# tenka1.net
KiCad netlist of a schematic drawn in EAGLE
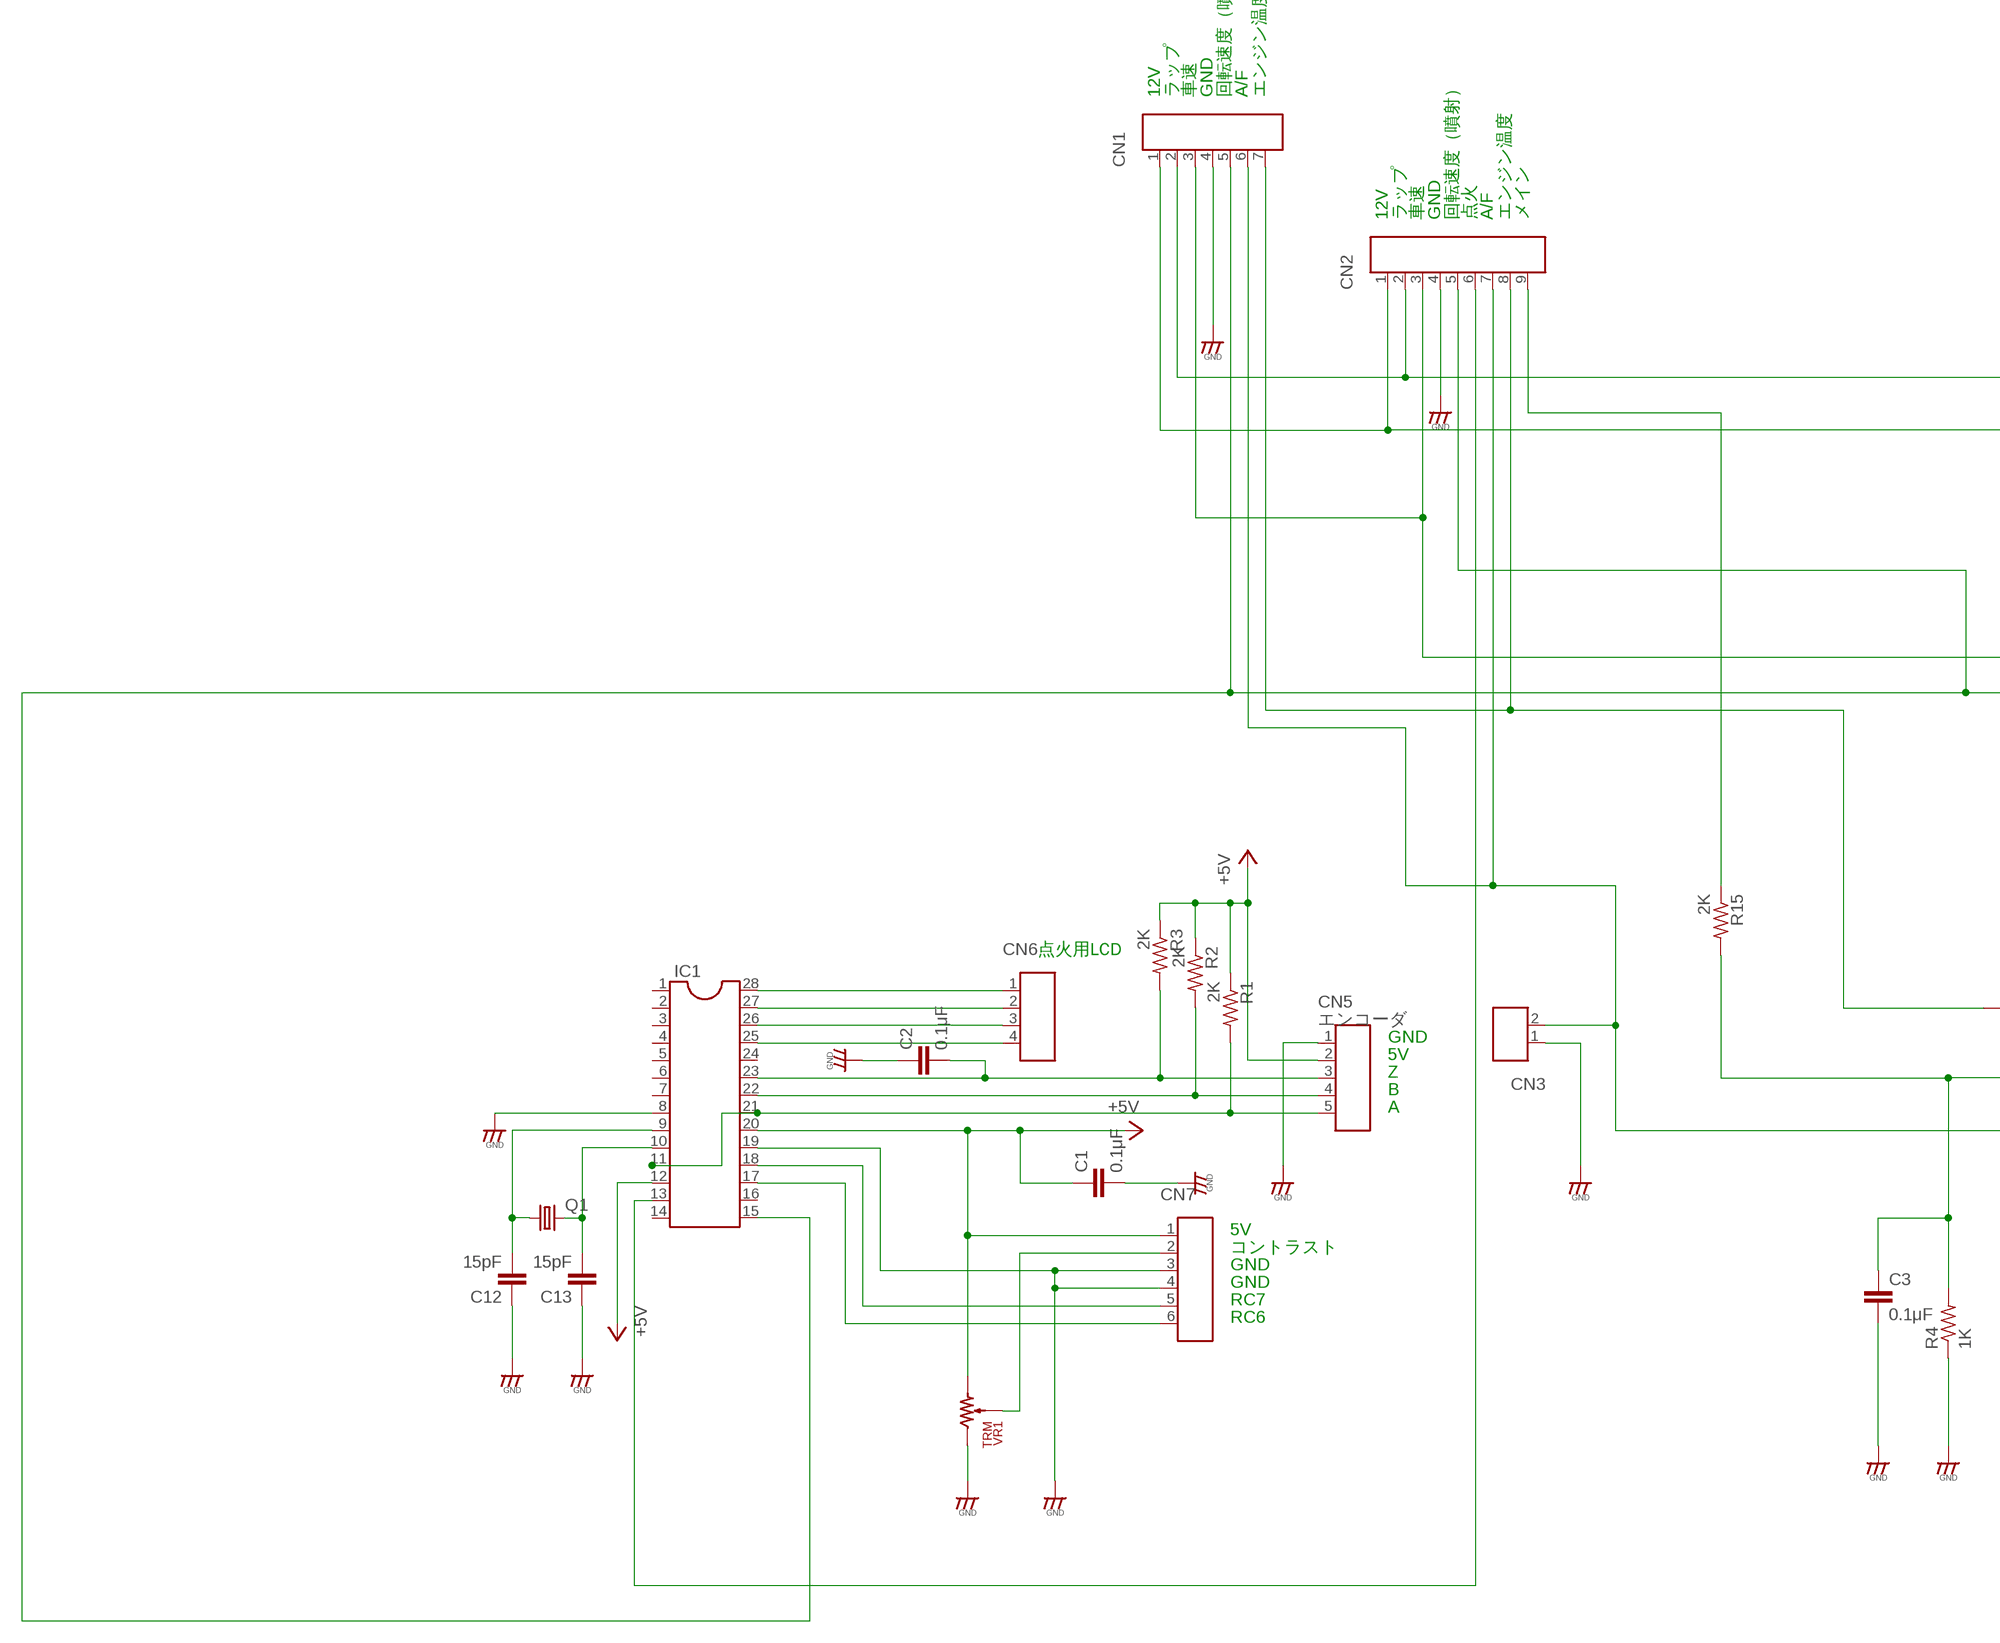
[diagram p0: schematic, sheet 1, part 1 of 2]
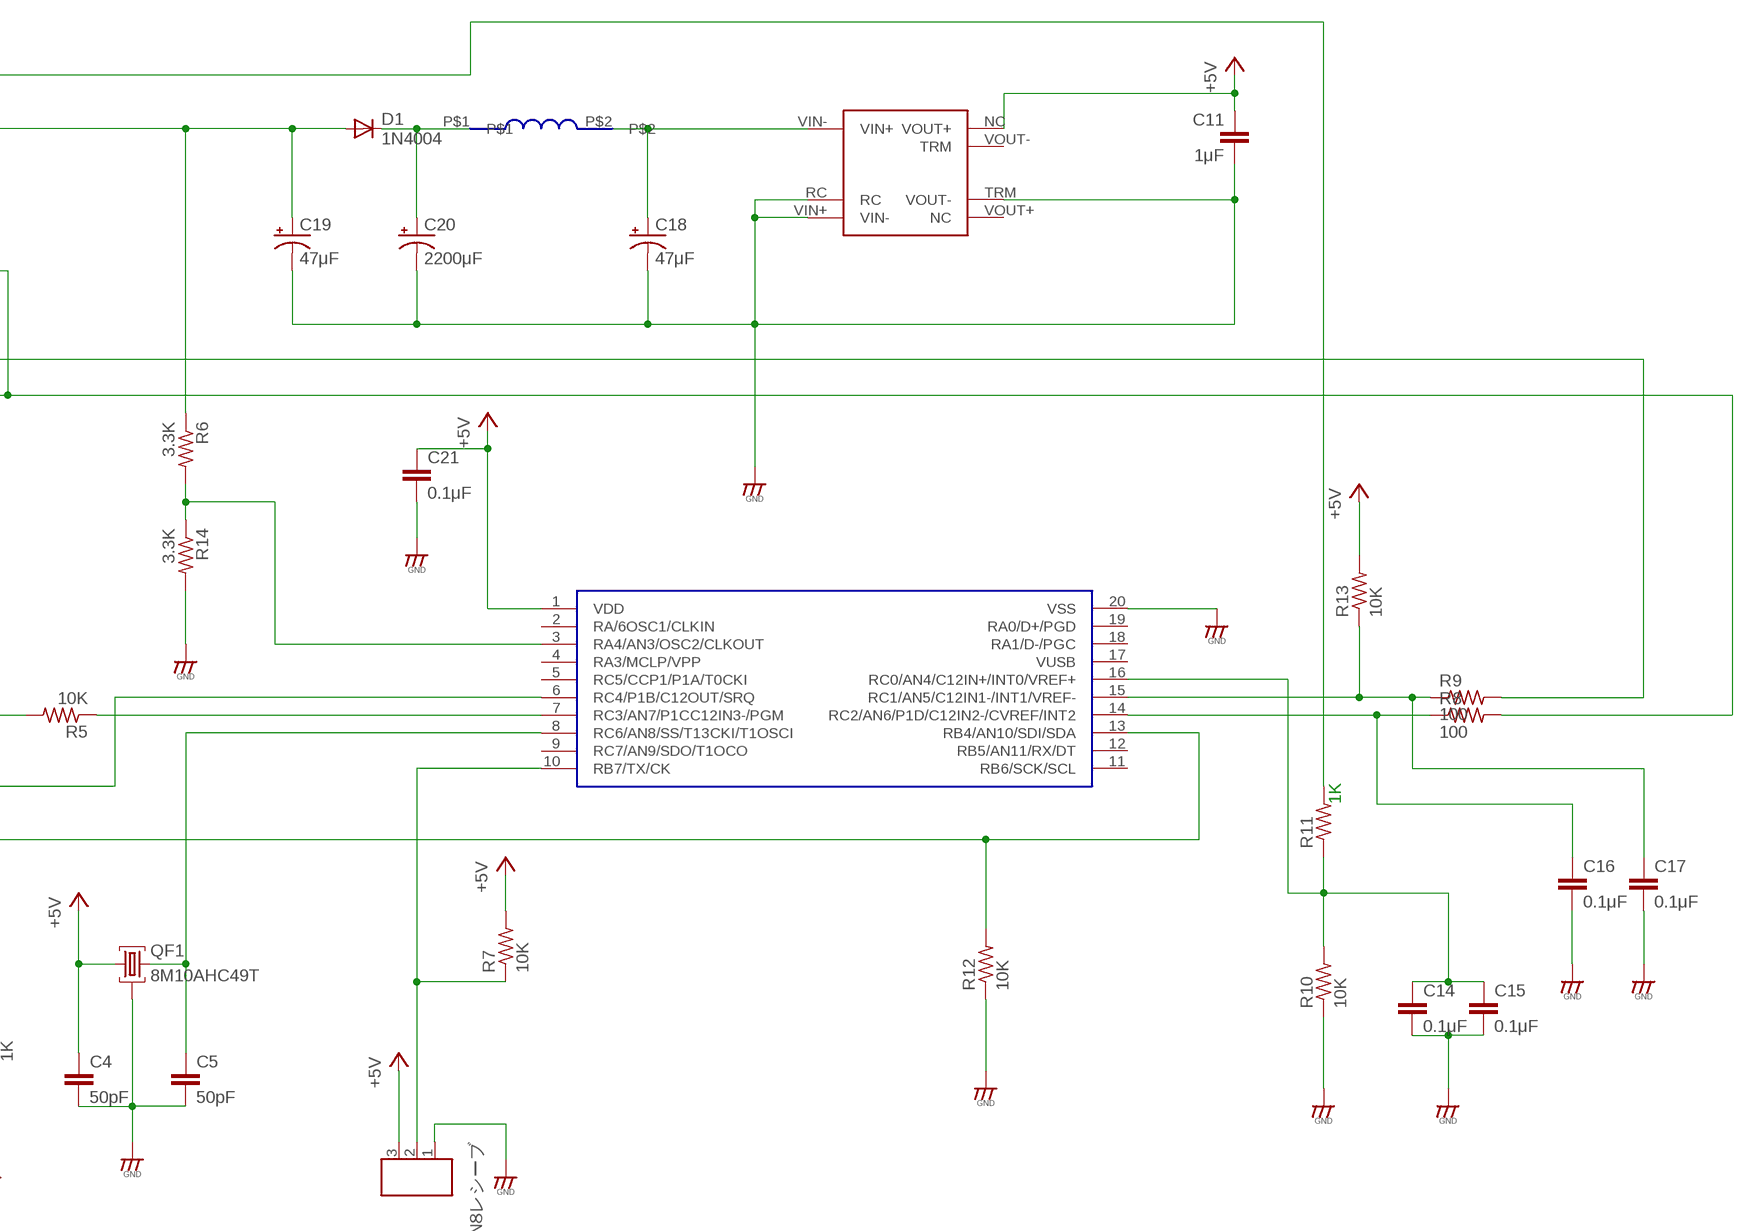
[diagram p1: schematic, sheet 1, part 2 of 2]

(export (version "E")
  (design (tool "Eeschema 10.0.6"))
  (components
    (comp (ref "18F14K50")
      (value "18F14K5018F14K50")
      (footprint "eagle-import:18F14K50")
      (libsource (lib "eagle-import") (part "18F14K5018F14K50"))
    )
    (comp (ref "C1")
      (value "0.1μF")
      (footprint "eagle-import:C025-024X044")
      (libsource (lib "eagle-import") (part "C-EU025-024X044"))
    )
    (comp (ref "C2")
      (value "0.1μF")
      (footprint "eagle-import:C025-024X044")
      (libsource (lib "eagle-import") (part "C-EU025-024X044"))
    )
    (comp (ref "C3")
      (value "0.1μF")
      (footprint "eagle-import:C025-024X044")
      (libsource (lib "eagle-import") (part "C-EU025-024X044"))
    )
    (comp (ref "C4")
      (value "50pF")
      (footprint "eagle-import:C025-024X044")
      (libsource (lib "eagle-import") (part "C-EU025-024X044"))
    )
    (comp (ref "C5")
      (value "50pF")
      (footprint "eagle-import:C025-024X044")
      (libsource (lib "eagle-import") (part "C-EU025-024X044"))
    )
    (comp (ref "C11")
      (value "1μF")
      (footprint "eagle-import:C025-024X044")
      (libsource (lib "eagle-import") (part "C-EU025-024X044"))
    )
    (comp (ref "C12")
      (value "15pF")
      (footprint "eagle-import:C025-024X044")
      (libsource (lib "eagle-import") (part "C-EU025-024X044"))
    )
    (comp (ref "C13")
      (value "15pF")
      (footprint "eagle-import:C025-024X044")
      (libsource (lib "eagle-import") (part "C-EU025-024X044"))
    )
    (comp (ref "C14")
      (value "0.1μF")
      (footprint "eagle-import:C025-024X044")
      (libsource (lib "eagle-import") (part "C-EU025-024X044"))
    )
    (comp (ref "C15")
      (value "0.1μF")
      (footprint "eagle-import:C025-024X044")
      (libsource (lib "eagle-import") (part "C-EU025-024X044"))
    )
    (comp (ref "C16")
      (value "0.1μF")
      (footprint "eagle-import:C025-024X044")
      (libsource (lib "eagle-import") (part "C-EU025-024X044"))
    )
    (comp (ref "C17")
      (value "0.1μF")
      (footprint "eagle-import:C025-024X044")
      (libsource (lib "eagle-import") (part "C-EU025-024X044"))
    )
    (comp (ref "C18")
      (value "47μF")
      (footprint "eagle-import:E2-4")
      (libsource (lib "eagle-import") (part "CPOL-USE2-4"))
    )
    (comp (ref "C19")
      (value "47μF")
      (footprint "eagle-import:E2-4")
      (libsource (lib "eagle-import") (part "CPOL-USE2-4"))
    )
    (comp (ref "C20")
      (value "2200μF")
      (footprint "eagle-import:E5-13")
      (libsource (lib "eagle-import") (part "CPOL-USE5-13"))
    )
    (comp (ref "C21")
      (value "0.1μF")
      (footprint "eagle-import:C025-024X044")
      (libsource (lib "eagle-import") (part "C-EU025-024X044"))
    )
    (comp (ref "CN1")
      (value "CON_7P")
      (footprint "eagle-import:CON_HRS_DIP_7")
      (libsource (lib "eagle-import") (part "CON_7P"))
    )
    (comp (ref "CN2")
      (value "CON_9P")
      (footprint "eagle-import:CON_HRS_DIP_9")
      (libsource (lib "eagle-import") (part "CON_9P"))
    )
    (comp (ref "CN3")
      (value "CON_2P")
      (footprint "eagle-import:CON_HRS_DIP_2")
      (libsource (lib "eagle-import") (part "CON_2P"))
    )
    (comp (ref "CN5")
      (value "エンコーダ")
      (footprint "eagle-import:CON_HRS_DIP_5")
      (libsource (lib "eagle-import") (part "CON_5P"))
    )
    (comp (ref "CN6")
      (value "CON_4P")
      (footprint "eagle-import:CON_HRS_DIP_4")
      (libsource (lib "eagle-import") (part "CON_4P"))
    )
    (comp (ref "CN7")
      (value "CON_6P")
      (footprint "eagle-import:CON_HRS_DIP_6")
      (libsource (lib "eagle-import") (part "CON_6P"))
    )
    (comp (ref "CN8レシーブ")
      (value "CON_3P")
      (footprint "eagle-import:CON_HRS_DIP_3")
      (libsource (lib "eagle-import") (part "CON_3P"))
    )
    (comp (ref "D1")
      (value "1N4004")
      (footprint "eagle-import:DO41-10")
      (libsource (lib "eagle-import") (part "1N4004"))
    )
    (comp (ref "DC2")
      (value "DCDC_NEW")
      (footprint "eagle-import:DCDC_NEW")
      (libsource (lib "eagle-import") (part "DCDC_NEW"))
    )
    (comp (ref "IC1")
      (value "DIL28-3")
      (footprint "eagle-import:DIL28-3")
      (libsource (lib "eagle-import") (part "DIL28-3"))
    )
    (comp (ref "LHL13NB101K1")
      (value "LHL13NB101KLHL13NB101K")
      (footprint "eagle-import:LHL13NB101K")
      (libsource (lib "eagle-import") (part "LHL13NB101KLHL13NB101K"))
    )
    (comp (ref "Q1")
      (value "CRYSTALHC49S")
      (footprint "eagle-import:HC49_S")
      (libsource (lib "eagle-import") (part "CRYSTALHC49S"))
    )
    (comp (ref "QF1")
      (value "8M10AHC49T")
      (footprint "eagle-import:HC49U")
      (libsource (lib "eagle-import") (part "8M10AHC49T"))
    )
    (comp (ref "R1")
      (value "2K")
      (footprint "eagle-import:0207_7")
      (libsource (lib "eagle-import") (part "R-US_0207/7"))
    )
    (comp (ref "R2")
      (value "2K")
      (footprint "eagle-import:0207_7")
      (libsource (lib "eagle-import") (part "R-US_0207/7"))
    )
    (comp (ref "R3")
      (value "2K")
      (footprint "eagle-import:0207_7")
      (libsource (lib "eagle-import") (part "R-US_0207/7"))
    )
    (comp (ref "R4")
      (value "1K")
      (footprint "eagle-import:0207_7")
      (libsource (lib "eagle-import") (part "R-US_0207/7"))
    )
    (comp (ref "R5")
      (value "10K")
      (footprint "eagle-import:0207_7")
      (libsource (lib "eagle-import") (part "R-US_0207/7"))
    )
    (comp (ref "R6")
      (value "3.3K")
      (footprint "eagle-import:0207_7")
      (libsource (lib "eagle-import") (part "R-US_0207/7"))
    )
    (comp (ref "R7")
      (value "10K")
      (footprint "eagle-import:0207_7")
      (libsource (lib "eagle-import") (part "R-US_0207/7"))
    )
    (comp (ref "R8")
      (value "100")
      (footprint "eagle-import:0207_7")
      (libsource (lib "eagle-import") (part "R-US_0207/7"))
    )
    (comp (ref "R9")
      (value "100")
      (footprint "eagle-import:0207_7")
      (libsource (lib "eagle-import") (part "R-US_0207/7"))
    )
    (comp (ref "R10")
      (value "10K")
      (footprint "eagle-import:0207_7")
      (libsource (lib "eagle-import") (part "R-US_0207/7"))
    )
    (comp (ref "R11")
      (value "R-US_0207/7")
      (footprint "eagle-import:0207_7")
      (libsource (lib "eagle-import") (part "R-US_0207/7"))
    )
    (comp (ref "R12")
      (value "10K")
      (footprint "eagle-import:0207_7")
      (libsource (lib "eagle-import") (part "R-US_0207/7"))
    )
    (comp (ref "R13")
      (value "10K")
      (footprint "eagle-import:0207_7")
      (libsource (lib "eagle-import") (part "R-US_0207/7"))
    )
    (comp (ref "R14")
      (value "3.3K")
      (footprint "eagle-import:0207_7")
      (libsource (lib "eagle-import") (part "R-US_0207/7"))
    )
    (comp (ref "R15")
      (value "2K")
      (footprint "eagle-import:0207_7")
      (libsource (lib "eagle-import") (part "R-US_0207/7"))
    )
    (comp (ref "VR1")
      (value "TRM")
      (footprint "eagle-import:TRM")
      (libsource (lib "eagle-import") (part "TRM"))
    )
  )
  (nets
    (net (code "1") (name "+5V") (class "Default")
      (node (ref "18F14K50") (pin "1") (pinfunction "VDD_1") (pintype "bidirectional"))
      (node (ref "C1") (pin "1") (pinfunction "1_1") (pintype "passive"))
      (node (ref "C11") (pin "1") (pinfunction "1_1") (pintype "passive"))
      (node (ref "C21") (pin "1") (pinfunction "1_1") (pintype "passive"))
      (node (ref "C4") (pin "1") (pinfunction "1_1") (pintype "passive"))
      (node (ref "CN5") (pin "2") (pinfunction "2_2") (pintype "passive"))
      (node (ref "CN7") (pin "1") (pinfunction "1_1") (pintype "passive"))
      (node (ref "CN8レシーブ") (pin "3") (pinfunction "3_3") (pintype "passive"))
      (node (ref "DC2") (pin "NC") (pinfunction "VOUT+_NC") (pintype "bidirectional"))
      (node (ref "IC1") (pin "12") (pinfunction "12_12") (pintype "passive"))
      (node (ref "IC1") (pin "20") (pinfunction "20_20") (pintype "passive"))
      (node (ref "QF1") (pin "1") (pinfunction "1_1") (pintype "passive"))
      (node (ref "R1") (pin "1") (pinfunction "1_1") (pintype "passive"))
      (node (ref "R13") (pin "2") (pinfunction "2_2") (pintype "passive"))
      (node (ref "R2") (pin "1") (pinfunction "1_1") (pintype "passive"))
      (node (ref "R3") (pin "1") (pinfunction "1_1") (pintype "passive"))
      (node (ref "R7") (pin "2") (pinfunction "2_2") (pintype "passive"))
      (node (ref "VR1") (pin "P$1") (pinfunction "P$1_P$1") (pintype "passive"))
    )
    (net (code "2") (name "GND") (class "Default")
      (node (ref "18F14K50") (pin "20") (pinfunction "VSS_20") (pintype "bidirectional"))
      (node (ref "C1") (pin "2") (pinfunction "2_2") (pintype "passive"))
      (node (ref "C11") (pin "2") (pinfunction "2_2") (pintype "passive"))
      (node (ref "C12") (pin "1") (pinfunction "1_1") (pintype "passive"))
      (node (ref "C13") (pin "1") (pinfunction "1_1") (pintype "passive"))
      (node (ref "C14") (pin "2") (pinfunction "2_2") (pintype "passive"))
      (node (ref "C15") (pin "2") (pinfunction "2_2") (pintype "passive"))
      (node (ref "C16") (pin "2") (pinfunction "2_2") (pintype "passive"))
      (node (ref "C17") (pin "2") (pinfunction "2_2") (pintype "passive"))
      (node (ref "C18") (pin "-") (pinfunction "-_-") (pintype "passive"))
      (node (ref "C19") (pin "-") (pinfunction "-_-") (pintype "passive"))
      (node (ref "C2") (pin "1") (pinfunction "1_1") (pintype "passive"))
      (node (ref "C20") (pin "-") (pinfunction "-_-") (pintype "passive"))
      (node (ref "C21") (pin "2") (pinfunction "2_2") (pintype "passive"))
      (node (ref "C3") (pin "2") (pinfunction "2_2") (pintype "passive"))
      (node (ref "C4") (pin "2") (pinfunction "2_2") (pintype "passive"))
      (node (ref "C5") (pin "2") (pinfunction "2_2") (pintype "passive"))
      (node (ref "CN1") (pin "4") (pinfunction "4_4") (pintype "passive"))
      (node (ref "CN2") (pin "4") (pinfunction "4_4") (pintype "passive"))
      (node (ref "CN3") (pin "1") (pinfunction "1_1") (pintype "passive"))
      (node (ref "CN5") (pin "1") (pinfunction "1_1") (pintype "passive"))
      (node (ref "CN7") (pin "3") (pinfunction "3_3") (pintype "passive"))
      (node (ref "CN7") (pin "4") (pinfunction "4_4") (pintype "passive"))
      (node (ref "CN8レシーブ") (pin "1") (pinfunction "1_1") (pintype "passive"))
      (node (ref "DC2") (pin "RC") (pinfunction "RC_RC") (pintype "bidirectional"))
      (node (ref "DC2") (pin "TRM") (pinfunction "VOUT-_TRM") (pintype "bidirectional"))
      (node (ref "DC2") (pin "VIN+") (pinfunction "VIN-_VIN+") (pintype "bidirectional"))
      (node (ref "IC1") (pin "19") (pinfunction "19_19") (pintype "passive"))
      (node (ref "IC1") (pin "8") (pinfunction "8_8") (pintype "passive"))
      (node (ref "QF1") (pin "2") (pinfunction "2_2") (pintype "passive"))
      (node (ref "R10") (pin "1") (pinfunction "1_1") (pintype "passive"))
      (node (ref "R12") (pin "1") (pinfunction "1_1") (pintype "passive"))
      (node (ref "R14") (pin "2") (pinfunction "2_2") (pintype "passive"))
      (node (ref "R4") (pin "1") (pinfunction "1_1") (pintype "passive"))
      (node (ref "VR1") (pin "P$3") (pinfunction "P$3_P$3") (pintype "passive"))
    )
    (net (code "3") (name "Net-(18F14K50-RA4{slash}AN3{slash}OSC2{slash}CLKOUT)") (class "Default")
      (node (ref "18F14K50") (pin "3") (pinfunction "RA4/AN3/OSC2/CLKOUT_3") (pintype "bidirectional"))
      (node (ref "R14") (pin "1") (pinfunction "1_1") (pintype "passive"))
      (node (ref "R6") (pin "2") (pinfunction "2_2") (pintype "passive"))
    )
    (net (code "4") (name "Net-(18F14K50-RB4{slash}AN10{slash}SDI{slash}SDA)") (class "Default")
      (node (ref "18F14K50") (pin "13") (pinfunction "RB4/AN10/SDI/SDA_13") (pintype "bidirectional"))
      (node (ref "CN1") (pin "6") (pinfunction "6_6") (pintype "passive"))
      (node (ref "CN2") (pin "7") (pinfunction "7_7") (pintype "passive"))
      (node (ref "CN3") (pin "2") (pinfunction "2_2") (pintype "passive"))
      (node (ref "R12") (pin "2") (pinfunction "2_2") (pintype "passive"))
    )
    (net (code "5") (name "Net-(18F14K50-RB7{slash}TX{slash}CK)") (class "Default")
      (node (ref "18F14K50") (pin "10") (pinfunction "RB7/TX/CK_10") (pintype "bidirectional"))
      (node (ref "CN8レシーブ") (pin "2") (pinfunction "2_2") (pintype "passive"))
      (node (ref "R7") (pin "1") (pinfunction "1_1") (pintype "passive"))
    )
    (net (code "6") (name "Net-(18F14K50-RC0{slash}AN4{slash}C12IN+{slash}INT0{slash}VREF+)") (class "Default")
      (node (ref "18F14K50") (pin "16") (pinfunction "RC0/AN4/C12IN+/INT0/VREF+_16") (pintype "bidirectional"))
      (node (ref "C14") (pin "1") (pinfunction "1_1") (pintype "passive"))
      (node (ref "C15") (pin "1") (pinfunction "1_1") (pintype "passive"))
      (node (ref "R10") (pin "2") (pinfunction "2_2") (pintype "passive"))
      (node (ref "R11") (pin "1") (pinfunction "1_1") (pintype "passive"))
    )
    (net (code "7") (name "Net-(18F14K50-RC1{slash}AN5{slash}C12IN1-{slash}INT1{slash}VREF-)") (class "Default")
      (node (ref "18F14K50") (pin "15") (pinfunction "RC1/AN5/C12IN1-/INT1/VREF-_15") (pintype "bidirectional"))
      (node (ref "C17") (pin "1") (pinfunction "1_1") (pintype "passive"))
      (node (ref "R13") (pin "1") (pinfunction "1_1") (pintype "passive"))
      (node (ref "R9") (pin "1") (pinfunction "1_1") (pintype "passive"))
    )
    (net (code "8") (name "Net-(18F14K50-RC2{slash}AN6{slash}P1D{slash}C12IN2-{slash}CVREF{slash}INT2)") (class "Default")
      (node (ref "18F14K50") (pin "14") (pinfunction "RC2/AN6/P1D/C12IN2-/CVREF/INT2_14") (pintype "bidirectional"))
      (node (ref "C16") (pin "1") (pinfunction "1_1") (pintype "passive"))
      (node (ref "R8") (pin "1") (pinfunction "1_1") (pintype "passive"))
    )
    (net (code "9") (name "Net-(18F14K50-RC3{slash}AN7{slash}P1CC12IN3-{slash}PGM)") (class "Default")
      (node (ref "18F14K50") (pin "7") (pinfunction "RC3/AN7/P1CC12IN3-/PGM_7") (pintype "bidirectional"))
      (node (ref "R5") (pin "1") (pinfunction "1_1") (pintype "passive"))
    )
    (net (code "10") (name "Net-(18F14K50-RC4{slash}P1B{slash}C12OUT{slash}SRQ)") (class "Default")
      (node (ref "18F14K50") (pin "6") (pinfunction "RC4/P1B/C12OUT/SRQ_6") (pintype "bidirectional"))
      (node (ref "C3") (pin "1") (pinfunction "1_1") (pintype "passive"))
      (node (ref "R15") (pin "2") (pinfunction "2_2") (pintype "passive"))
      (node (ref "R4") (pin "2") (pinfunction "2_2") (pintype "passive"))
    )
    (net (code "11") (name "Net-(18F14K50-RC6{slash}AN8{slash}SS{slash}T13CKI{slash}T1OSCI)") (class "Default")
      (node (ref "18F14K50") (pin "8") (pinfunction "RC6/AN8/SS/T13CKI/T1OSCI_8") (pintype "bidirectional"))
      (node (ref "C5") (pin "1") (pinfunction "1_1") (pintype "passive"))
      (node (ref "QF1") (pin "3") (pinfunction "3_3") (pintype "passive"))
    )
    (net (code "12") (name "Net-(C2-Pad2)") (class "Default")
      (node (ref "C2") (pin "2") (pinfunction "2_2") (pintype "passive"))
      (node (ref "CN5") (pin "3") (pinfunction "3_3") (pintype "passive"))
      (node (ref "IC1") (pin "23") (pinfunction "23_23") (pintype "passive"))
      (node (ref "R3") (pin "2") (pinfunction "2_2") (pintype "passive"))
    )
    (net (code "13") (name "Net-(C12-Pad2)") (class "Default")
      (node (ref "C12") (pin "2") (pinfunction "2_2") (pintype "passive"))
      (node (ref "IC1") (pin "9") (pinfunction "9_9") (pintype "passive"))
      (node (ref "Q1") (pin "1") (pinfunction "1_1") (pintype "passive"))
    )
    (net (code "14") (name "Net-(C13-Pad2)") (class "Default")
      (node (ref "C13") (pin "2") (pinfunction "2_2") (pintype "passive"))
      (node (ref "IC1") (pin "10") (pinfunction "10_10") (pintype "passive"))
      (node (ref "Q1") (pin "2") (pinfunction "2_2") (pintype "passive"))
    )
    (net (code "15") (name "Net-(C19-Pad+)") (class "Default")
      (node (ref "C19") (pin "+") (pinfunction "+_+") (pintype "passive"))
      (node (ref "CN1") (pin "1") (pinfunction "1_1") (pintype "passive"))
      (node (ref "CN2") (pin "1") (pinfunction "1_1") (pintype "passive"))
      (node (ref "D1") (pin "A") (pinfunction "A_A") (pintype "passive"))
      (node (ref "R6") (pin "1") (pinfunction "1_1") (pintype "passive"))
    )
    (net (code "16") (name "Net-(C20-Pad+)") (class "Default")
      (node (ref "C20") (pin "+") (pinfunction "+_+") (pintype "passive"))
      (node (ref "D1") (pin "C") (pinfunction "C_C") (pintype "passive"))
      (node (ref "LHL13NB101K1") (pin "P$1") (pinfunction "P$1_P$1") (pintype "bidirectional"))
    )
    (net (code "17") (name "Net-(CN1-Pad2)") (class "Default")
      (node (ref "CN1") (pin "2") (pinfunction "2_2") (pintype "passive"))
      (node (ref "CN2") (pin "2") (pinfunction "2_2") (pintype "passive"))
      (node (ref "R11") (pin "2") (pinfunction "2_2") (pintype "passive"))
    )
    (net (code "18") (name "Net-(CN1-Pad3)") (class "Default")
      (node (ref "CN1") (pin "3") (pinfunction "3_3") (pintype "passive"))
      (node (ref "CN2") (pin "3") (pinfunction "3_3") (pintype "passive"))
      (node (ref "R9") (pin "2") (pinfunction "2_2") (pintype "passive"))
    )
    (net (code "19") (name "Net-(CN1-Pad5)") (class "Default")
      (node (ref "CN1") (pin "5") (pinfunction "5_5") (pintype "passive"))
      (node (ref "CN2") (pin "5") (pinfunction "5_5") (pintype "passive"))
      (node (ref "IC1") (pin "15") (pinfunction "15_15") (pintype "passive"))
      (node (ref "R8") (pin "2") (pinfunction "2_2") (pintype "passive"))
    )
    (net (code "20") (name "Net-(CN1-Pad7)") (class "Default")
      (node (ref "CN1") (pin "7") (pinfunction "7_7") (pintype "passive"))
      (node (ref "CN2") (pin "8") (pinfunction "8_8") (pintype "passive"))
      (node (ref "R5") (pin "2") (pinfunction "2_2") (pintype "passive"))
    )
    (net (code "21") (name "Net-(CN2-Pad6)") (class "Default")
      (node (ref "CN2") (pin "6") (pinfunction "6_6") (pintype "passive"))
      (node (ref "IC1") (pin "13") (pinfunction "13_13") (pintype "passive"))
    )
    (net (code "22") (name "Net-(CN2-Pad9)") (class "Default")
      (node (ref "CN2") (pin "9") (pinfunction "9_9") (pintype "passive"))
      (node (ref "R15") (pin "1") (pinfunction "1_1") (pintype "passive"))
    )
    (net (code "23") (name "Net-(CN5-Pad4)") (class "Default")
      (node (ref "CN5") (pin "4") (pinfunction "4_4") (pintype "passive"))
      (node (ref "IC1") (pin "22") (pinfunction "22_22") (pintype "passive"))
      (node (ref "R2") (pin "2") (pinfunction "2_2") (pintype "passive"))
    )
    (net (code "24") (name "Net-(CN5-Pad5)") (class "Default")
      (node (ref "CN5") (pin "5") (pinfunction "5_5") (pintype "passive"))
      (node (ref "IC1") (pin "11") (pinfunction "11_11") (pintype "passive"))
      (node (ref "IC1") (pin "21") (pinfunction "21_21") (pintype "passive"))
      (node (ref "R1") (pin "2") (pinfunction "2_2") (pintype "passive"))
    )
    (net (code "25") (name "Net-(CN6-Pad1)") (class "Default")
      (node (ref "CN6") (pin "1") (pinfunction "1_1") (pintype "passive"))
      (node (ref "IC1") (pin "28") (pinfunction "28_28") (pintype "passive"))
    )
    (net (code "26") (name "Net-(CN6-Pad2)") (class "Default")
      (node (ref "CN6") (pin "2") (pinfunction "2_2") (pintype "passive"))
      (node (ref "IC1") (pin "27") (pinfunction "27_27") (pintype "passive"))
    )
    (net (code "27") (name "Net-(CN6-Pad3)") (class "Default")
      (node (ref "CN6") (pin "3") (pinfunction "3_3") (pintype "passive"))
      (node (ref "IC1") (pin "26") (pinfunction "26_26") (pintype "passive"))
    )
    (net (code "28") (name "Net-(CN6-Pad4)") (class "Default")
      (node (ref "CN6") (pin "4") (pinfunction "4_4") (pintype "passive"))
      (node (ref "IC1") (pin "25") (pinfunction "25_25") (pintype "passive"))
    )
    (net (code "29") (name "Net-(CN7-Pad2)") (class "Default")
      (node (ref "CN7") (pin "2") (pinfunction "2_2") (pintype "passive"))
      (node (ref "VR1") (pin "P$2") (pinfunction "P$2_P$2") (pintype "passive"))
    )
    (net (code "30") (name "Net-(CN7-Pad5)") (class "Default")
      (node (ref "CN7") (pin "5") (pinfunction "5_5") (pintype "passive"))
      (node (ref "IC1") (pin "18") (pinfunction "18_18") (pintype "passive"))
    )
    (net (code "31") (name "Net-(CN7-Pad6)") (class "Default")
      (node (ref "CN7") (pin "6") (pinfunction "6_6") (pintype "passive"))
      (node (ref "IC1") (pin "17") (pinfunction "17_17") (pintype "passive"))
    )
    (net (code "32") (name "Net-(DC2-VIN+)") (class "Default")
      (node (ref "C18") (pin "+") (pinfunction "+_+") (pintype "passive"))
      (node (ref "DC2") (pin "VIN-") (pinfunction "VIN+_VIN-") (pintype "bidirectional"))
      (node (ref "LHL13NB101K1") (pin "P$2") (pinfunction "P$2_P$2") (pintype "bidirectional"))
    )
    (net (code "33") (name "unconnected-(18F14K50-RA0{slash}D+{slash}PGD-Pad19)") (class "Default")
      (node (ref "18F14K50") (pin "19") (pinfunction "RA0/D+/PGD_19") (pintype "bidirectional"))
    )
    (net (code "34") (name "unconnected-(18F14K50-RA1{slash}D-{slash}PGC-Pad18)") (class "Default")
      (node (ref "18F14K50") (pin "18") (pinfunction "RA1/D-/PGC_18") (pintype "bidirectional"))
    )
    (net (code "35") (name "unconnected-(18F14K50-RA3{slash}MCLP{slash}VPP-Pad4)") (class "Default")
      (node (ref "18F14K50") (pin "4") (pinfunction "RA3/MCLP/VPP_4") (pintype "bidirectional"))
    )
    (net (code "36") (name "unconnected-(18F14K50-RA{slash}6OSC1{slash}CLKIN-Pad2)") (class "Default")
      (node (ref "18F14K50") (pin "2") (pinfunction "RA/6OSC1/CLKIN_2") (pintype "bidirectional"))
    )
    (net (code "37") (name "unconnected-(18F14K50-RB5{slash}AN11{slash}RX{slash}DT-Pad12)") (class "Default")
      (node (ref "18F14K50") (pin "12") (pinfunction "RB5/AN11/RX/DT_12") (pintype "bidirectional"))
    )
    (net (code "38") (name "unconnected-(18F14K50-RB6{slash}SCK{slash}SCL-Pad11)") (class "Default")
      (node (ref "18F14K50") (pin "11") (pinfunction "RB6/SCK/SCL_11") (pintype "bidirectional"))
    )
    (net (code "39") (name "unconnected-(18F14K50-RC5{slash}CCP1{slash}P1A{slash}T0CKI-Pad5)") (class "Default")
      (node (ref "18F14K50") (pin "5") (pinfunction "RC5/CCP1/P1A/T0CKI_5") (pintype "bidirectional"))
    )
    (net (code "40") (name "unconnected-(18F14K50-RC7{slash}AN9{slash}SDO{slash}T1OCO-Pad9)") (class "Default")
      (node (ref "18F14K50") (pin "9") (pinfunction "RC7/AN9/SDO/T1OCO_9") (pintype "bidirectional"))
    )
    (net (code "41") (name "unconnected-(18F14K50-VUSB-Pad17)") (class "Default")
      (node (ref "18F14K50") (pin "17") (pinfunction "VUSB_17") (pintype "bidirectional"))
    )
    (net (code "42") (name "unconnected-(DC2-NC-PadVOUT+)") (class "Default")
      (node (ref "DC2") (pin "VOUT+") (pinfunction "NC_VOUT+") (pintype "bidirectional"))
    )
    (net (code "43") (name "unconnected-(DC2-TRM-PadVOUT-)") (class "Default")
      (node (ref "DC2") (pin "VOUT-") (pinfunction "TRM_VOUT-") (pintype "bidirectional"))
    )
    (net (code "44") (name "unconnected-(IC1-Pad1)") (class "Default")
      (node (ref "IC1") (pin "1") (pinfunction "1_1") (pintype "passive"))
    )
    (net (code "45") (name "unconnected-(IC1-Pad2)") (class "Default")
      (node (ref "IC1") (pin "2") (pinfunction "2_2") (pintype "passive"))
    )
    (net (code "46") (name "unconnected-(IC1-Pad3)") (class "Default")
      (node (ref "IC1") (pin "3") (pinfunction "3_3") (pintype "passive"))
    )
    (net (code "47") (name "unconnected-(IC1-Pad4)") (class "Default")
      (node (ref "IC1") (pin "4") (pinfunction "4_4") (pintype "passive"))
    )
    (net (code "48") (name "unconnected-(IC1-Pad5)") (class "Default")
      (node (ref "IC1") (pin "5") (pinfunction "5_5") (pintype "passive"))
    )
    (net (code "49") (name "unconnected-(IC1-Pad6)") (class "Default")
      (node (ref "IC1") (pin "6") (pinfunction "6_6") (pintype "passive"))
    )
    (net (code "50") (name "unconnected-(IC1-Pad7)") (class "Default")
      (node (ref "IC1") (pin "7") (pinfunction "7_7") (pintype "passive"))
    )
    (net (code "51") (name "unconnected-(IC1-Pad14)") (class "Default")
      (node (ref "IC1") (pin "14") (pinfunction "14_14") (pintype "passive"))
    )
    (net (code "52") (name "unconnected-(IC1-Pad16)") (class "Default")
      (node (ref "IC1") (pin "16") (pinfunction "16_16") (pintype "passive"))
    )
    (net (code "53") (name "unconnected-(IC1-Pad24)") (class "Default")
      (node (ref "IC1") (pin "24") (pinfunction "24_24") (pintype "passive"))
    )
  )
)
